# discodolly.net
KiCad netlist of a schematic drawn in EAGLE
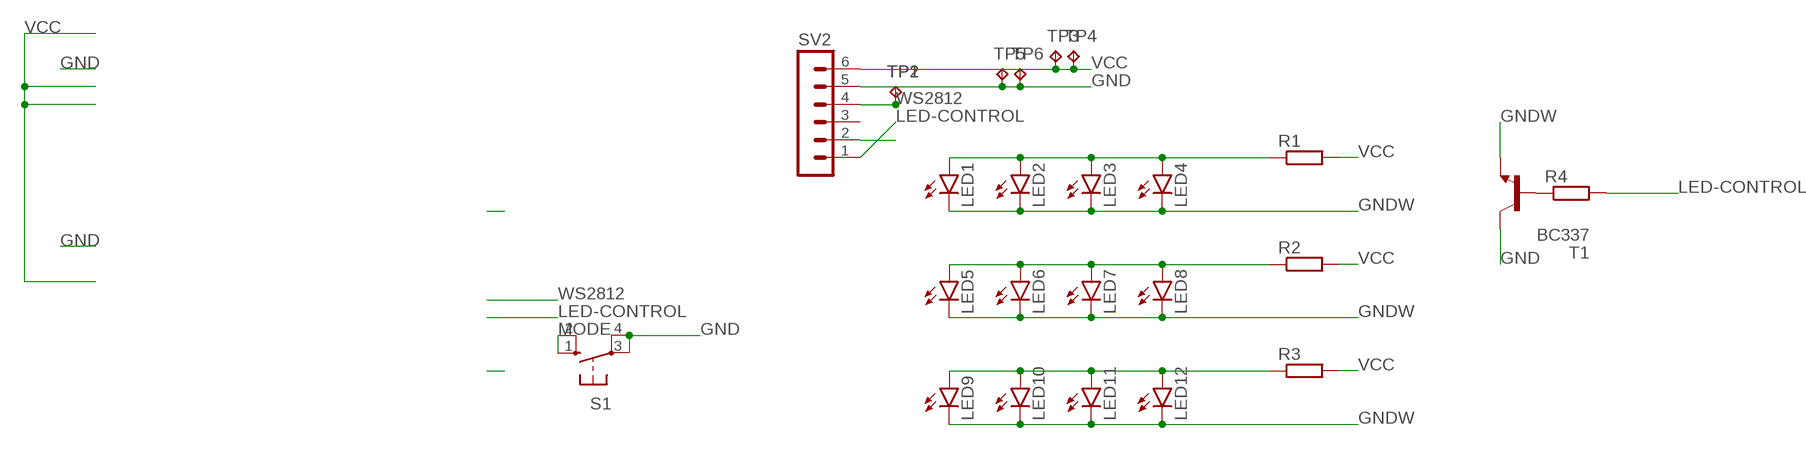
[diagram p0: schematic, sheet 1]

(export (version "E")
  (design (tool "Eeschema 10.0.6"))
  (components
    (comp (ref "LED1")
      (value "LEDCHIPLED_1206")
      (footprint "eagle-import:CHIPLED_1206")
      (libsource (lib "eagle-import") (part "LEDCHIPLED_1206"))
    )
    (comp (ref "LED2")
      (value "LEDCHIPLED_1206")
      (footprint "eagle-import:CHIPLED_1206")
      (libsource (lib "eagle-import") (part "LEDCHIPLED_1206"))
    )
    (comp (ref "LED3")
      (value "LEDCHIPLED_1206")
      (footprint "eagle-import:CHIPLED_1206")
      (libsource (lib "eagle-import") (part "LEDCHIPLED_1206"))
    )
    (comp (ref "LED4")
      (value "LEDCHIPLED_1206")
      (footprint "eagle-import:CHIPLED_1206")
      (libsource (lib "eagle-import") (part "LEDCHIPLED_1206"))
    )
    (comp (ref "LED5")
      (value "LEDCHIPLED_1206")
      (footprint "eagle-import:CHIPLED_1206")
      (libsource (lib "eagle-import") (part "LEDCHIPLED_1206"))
    )
    (comp (ref "LED6")
      (value "LEDCHIPLED_1206")
      (footprint "eagle-import:CHIPLED_1206")
      (libsource (lib "eagle-import") (part "LEDCHIPLED_1206"))
    )
    (comp (ref "LED7")
      (value "LEDCHIPLED_1206")
      (footprint "eagle-import:CHIPLED_1206")
      (libsource (lib "eagle-import") (part "LEDCHIPLED_1206"))
    )
    (comp (ref "LED8")
      (value "LEDCHIPLED_1206")
      (footprint "eagle-import:CHIPLED_1206")
      (libsource (lib "eagle-import") (part "LEDCHIPLED_1206"))
    )
    (comp (ref "LED9")
      (value "LEDCHIPLED_1206")
      (footprint "eagle-import:CHIPLED_1206")
      (libsource (lib "eagle-import") (part "LEDCHIPLED_1206"))
    )
    (comp (ref "LED10")
      (value "LEDCHIPLED_1206")
      (footprint "eagle-import:CHIPLED_1206")
      (libsource (lib "eagle-import") (part "LEDCHIPLED_1206"))
    )
    (comp (ref "LED11")
      (value "LEDCHIPLED_1206")
      (footprint "eagle-import:CHIPLED_1206")
      (libsource (lib "eagle-import") (part "LEDCHIPLED_1206"))
    )
    (comp (ref "LED12")
      (value "LEDCHIPLED_1206")
      (footprint "eagle-import:CHIPLED_1206")
      (libsource (lib "eagle-import") (part "LEDCHIPLED_1206"))
    )
    (comp (ref "R1")
      (value "R-EU_M1206")
      (footprint "eagle-import:M1206")
      (libsource (lib "eagle-import") (part "R-EU_M1206"))
    )
    (comp (ref "R2")
      (value "R-EU_M1206")
      (footprint "eagle-import:M1206")
      (libsource (lib "eagle-import") (part "R-EU_M1206"))
    )
    (comp (ref "R3")
      (value "R-EU_M1206")
      (footprint "eagle-import:M1206")
      (libsource (lib "eagle-import") (part "R-EU_M1206"))
    )
    (comp (ref "R4")
      (value "R-EU_M1206")
      (footprint "eagle-import:M1206")
      (libsource (lib "eagle-import") (part "R-EU_M1206"))
    )
    (comp (ref "S1")
      (value "10-XX")
      (footprint "eagle-import:B3F-10XX")
      (fields (field (name "MPN") "B3F-1000"))
      (libsource (lib "eagle-import") (part "10-XX"))
    )
    (comp (ref "SV2")
      (value "MA06-1")
      (footprint "eagle-import:MA06-1")
      (libsource (lib "eagle-import") (part "MA06-1"))
    )
    (comp (ref "T1")
      (value "BC337")
      (footprint "eagle-import:TO92")
      (libsource (lib "eagle-import") (part "BC337"))
    )
    (comp (ref "TP1")
      (value "TPTP20SQ")
      (footprint "eagle-import:TP20SQ")
      (libsource (lib "eagle-import") (part "TPTP20SQ"))
    )
    (comp (ref "TP2")
      (value "TPTP20SQ")
      (footprint "eagle-import:TP20SQ")
      (libsource (lib "eagle-import") (part "TPTP20SQ"))
    )
    (comp (ref "TP3")
      (value "TPTP20SQ")
      (footprint "eagle-import:TP20SQ")
      (libsource (lib "eagle-import") (part "TPTP20SQ"))
    )
    (comp (ref "TP4")
      (value "TPTP20SQ")
      (footprint "eagle-import:TP20SQ")
      (libsource (lib "eagle-import") (part "TPTP20SQ"))
    )
    (comp (ref "TP5")
      (value "TPTP20SQ")
      (footprint "eagle-import:TP20SQ")
      (libsource (lib "eagle-import") (part "TPTP20SQ"))
    )
    (comp (ref "TP6")
      (value "TPTP20SQ")
      (footprint "eagle-import:TP20SQ")
      (libsource (lib "eagle-import") (part "TPTP20SQ"))
    )
  )
  (nets
    (net (code "1") (name "/GND") (class "Default")
      (node (ref "S1") (pin "3") (pinfunction "P_3") (pintype "passive"))
      (node (ref "S1") (pin "4") (pinfunction "P1_4") (pintype "passive"))
      (node (ref "SV2") (pin "5") (pinfunction "5_5") (pintype "passive"))
      (node (ref "T1") (pin "3") (pinfunction "C_3") (pintype "passive"))
      (node (ref "TP5") (pin "TP") (pinfunction "TP_TP") (pintype "input"))
      (node (ref "TP6") (pin "TP") (pinfunction "TP_TP") (pintype "input"))
    )
    (net (code "2") (name "/GNDW") (class "Default")
      (node (ref "LED1") (pin "C") (pinfunction "C_C") (pintype "passive"))
      (node (ref "LED10") (pin "C") (pinfunction "C_C") (pintype "passive"))
      (node (ref "LED11") (pin "C") (pinfunction "C_C") (pintype "passive"))
      (node (ref "LED12") (pin "C") (pinfunction "C_C") (pintype "passive"))
      (node (ref "LED2") (pin "C") (pinfunction "C_C") (pintype "passive"))
      (node (ref "LED3") (pin "C") (pinfunction "C_C") (pintype "passive"))
      (node (ref "LED4") (pin "C") (pinfunction "C_C") (pintype "passive"))
      (node (ref "LED5") (pin "C") (pinfunction "C_C") (pintype "passive"))
      (node (ref "LED6") (pin "C") (pinfunction "C_C") (pintype "passive"))
      (node (ref "LED7") (pin "C") (pinfunction "C_C") (pintype "passive"))
      (node (ref "LED8") (pin "C") (pinfunction "C_C") (pintype "passive"))
      (node (ref "LED9") (pin "C") (pinfunction "C_C") (pintype "passive"))
      (node (ref "T1") (pin "1") (pinfunction "E_1") (pintype "passive"))
    )
    (net (code "3") (name "/LED-CONTROL") (class "Default")
      (node (ref "R4") (pin "2") (pinfunction "2_2") (pintype "passive"))
      (node (ref "SV2") (pin "1") (pinfunction "1_1") (pintype "passive"))
    )
    (net (code "4") (name "/MODE") (class "Default")
      (node (ref "S1") (pin "1") (pinfunction "S_1") (pintype "passive"))
      (node (ref "S1") (pin "2") (pinfunction "S1_2") (pintype "passive"))
      (node (ref "SV2") (pin "2") (pinfunction "2_2") (pintype "passive"))
    )
    (net (code "5") (name "/VCC") (class "Default")
      (node (ref "R1") (pin "2") (pinfunction "2_2") (pintype "passive"))
      (node (ref "R2") (pin "2") (pinfunction "2_2") (pintype "passive"))
      (node (ref "R3") (pin "2") (pinfunction "2_2") (pintype "passive"))
      (node (ref "SV2") (pin "6") (pinfunction "6_6") (pintype "passive"))
      (node (ref "TP3") (pin "TP") (pinfunction "TP_TP") (pintype "input"))
      (node (ref "TP4") (pin "TP") (pinfunction "TP_TP") (pintype "input"))
    )
    (net (code "6") (name "/WS2812") (class "Default")
      (node (ref "SV2") (pin "4") (pinfunction "4_4") (pintype "passive"))
      (node (ref "TP1") (pin "TP") (pinfunction "TP_TP") (pintype "input"))
      (node (ref "TP2") (pin "TP") (pinfunction "TP_TP") (pintype "input"))
    )
    (net (code "7") (name "Net-(LED1-PadA)") (class "Default")
      (node (ref "LED1") (pin "A") (pinfunction "A_A") (pintype "passive"))
      (node (ref "LED2") (pin "A") (pinfunction "A_A") (pintype "passive"))
      (node (ref "LED3") (pin "A") (pinfunction "A_A") (pintype "passive"))
      (node (ref "LED4") (pin "A") (pinfunction "A_A") (pintype "passive"))
      (node (ref "R1") (pin "1") (pinfunction "1_1") (pintype "passive"))
    )
    (net (code "8") (name "Net-(LED5-PadA)") (class "Default")
      (node (ref "LED5") (pin "A") (pinfunction "A_A") (pintype "passive"))
      (node (ref "LED6") (pin "A") (pinfunction "A_A") (pintype "passive"))
      (node (ref "LED7") (pin "A") (pinfunction "A_A") (pintype "passive"))
      (node (ref "LED8") (pin "A") (pinfunction "A_A") (pintype "passive"))
      (node (ref "R2") (pin "1") (pinfunction "1_1") (pintype "passive"))
    )
    (net (code "9") (name "Net-(LED10-PadA)") (class "Default")
      (node (ref "LED10") (pin "A") (pinfunction "A_A") (pintype "passive"))
      (node (ref "LED11") (pin "A") (pinfunction "A_A") (pintype "passive"))
      (node (ref "LED12") (pin "A") (pinfunction "A_A") (pintype "passive"))
      (node (ref "LED9") (pin "A") (pinfunction "A_A") (pintype "passive"))
      (node (ref "R3") (pin "1") (pinfunction "1_1") (pintype "passive"))
    )
    (net (code "10") (name "Net-(T1-B)") (class "Default")
      (node (ref "R4") (pin "1") (pinfunction "1_1") (pintype "passive"))
      (node (ref "T1") (pin "2") (pinfunction "B_2") (pintype "passive"))
    )
    (net (code "11") (name "unconnected-(SV2-Pad3)") (class "Default")
      (node (ref "SV2") (pin "3") (pinfunction "3_3") (pintype "passive"))
    )
  )
)
